# protoboard.net
KiCad netlist of a schematic drawn in EAGLE
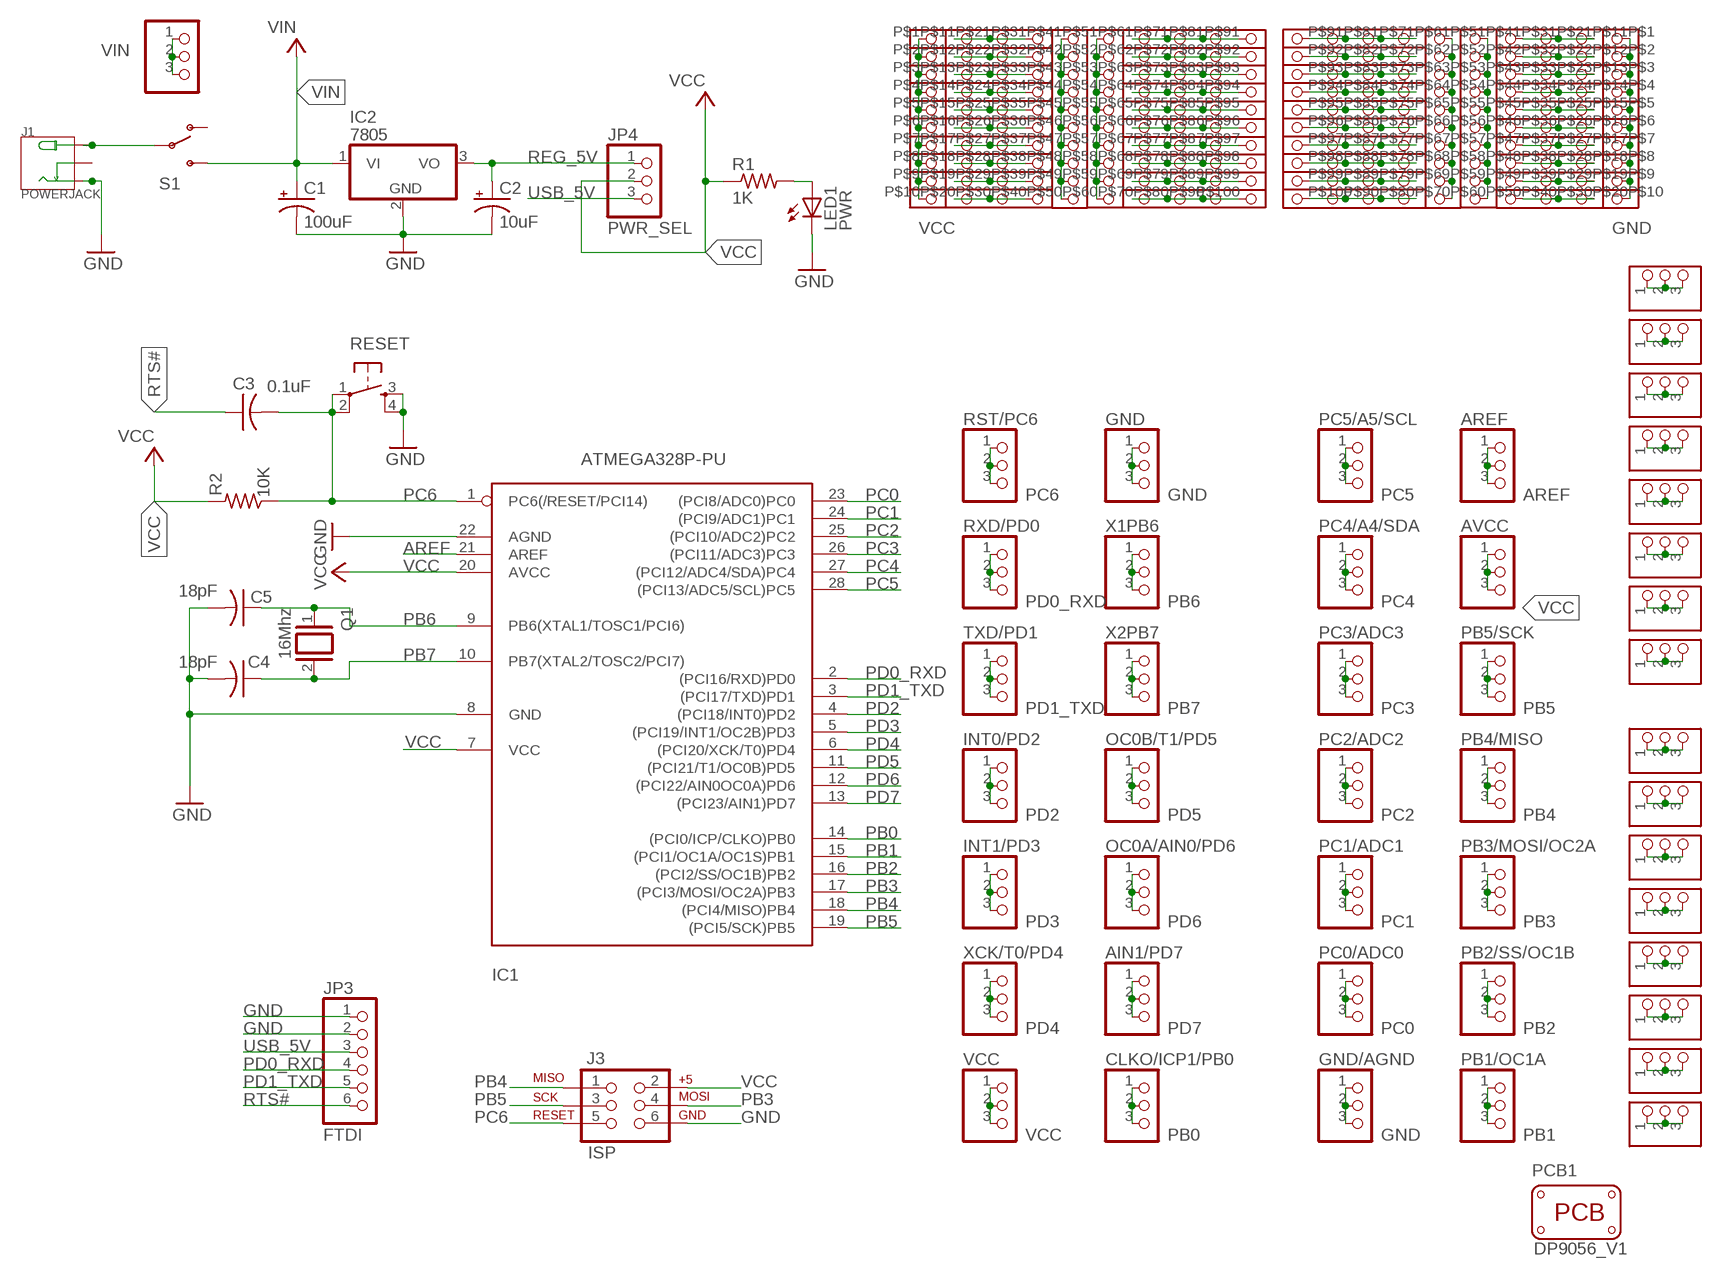
[diagram p0: schematic, sheet 1]

(export (version "E")
  (design (tool "Eeschema 10.0.6"))
  (components
    (comp (ref "AIN1/PD7")
      (value "PINHD-1X3")
      (footprint "eagle-import:1X03")
      (libsource (lib "eagle-import") (part "ubiyubix_PINHD-1X3"))
    )
    (comp (ref "AREF")
      (value "PINHD-1X3")
      (footprint "eagle-import:1X03")
      (libsource (lib "eagle-import") (part "ubiyubix_PINHD-1X3"))
    )
    (comp (ref "AVCC")
      (value "PINHD-1X3")
      (footprint "eagle-import:1X03")
      (libsource (lib "eagle-import") (part "ubiyubix_PINHD-1X3"))
    )
    (comp (ref "C1")
      (value "100uF")
      (footprint "eagle-import:CPOL-RADIAL-100UF-25V")
      (libsource (lib "eagle-import") (part "CAP_POLPTH1"))
    )
    (comp (ref "C2")
      (value "10uF")
      (footprint "eagle-import:CPOL-RADIAL-10UF-25V")
      (libsource (lib "eagle-import") (part "CAP_POLPTH2"))
    )
    (comp (ref "C3")
      (value "0.1uF")
      (footprint "eagle-import:C025-025X050")
      (libsource (lib "eagle-import") (part "C-US025-025X050"))
    )
    (comp (ref "C4")
      (value "18pF")
      (footprint "eagle-import:C025-025X050")
      (libsource (lib "eagle-import") (part "C-US025-025X050"))
    )
    (comp (ref "C5")
      (value "18pF")
      (footprint "eagle-import:C025-025X050")
      (libsource (lib "eagle-import") (part "C-US025-025X050"))
    )
    (comp (ref "CLKO/ICP1/PB0")
      (value "PINHD-1X3")
      (footprint "eagle-import:1X03")
      (libsource (lib "eagle-import") (part "ubiyubix_PINHD-1X3"))
    )
    (comp (ref "GND")
      (value "PINHD-1X3")
      (footprint "eagle-import:1X03")
      (libsource (lib "eagle-import") (part "ubiyubix_PINHD-1X3"))
    )
    (comp (ref "GND/AGND")
      (value "PINHD-1X3")
      (footprint "eagle-import:1X03")
      (libsource (lib "eagle-import") (part "ubiyubix_PINHD-1X3"))
    )
    (comp (ref "IC1")
      (value "ATMEGA328P-PU")
      (footprint "eagle-import:DIL28-3")
      (libsource (lib "eagle-import") (part "ATMEGA168P-20"))
    )
    (comp (ref "IC2")
      (value "7805")
      (footprint "eagle-import:TO220H")
      (libsource (lib "eagle-import") (part "78T05"))
    )
    (comp (ref "INT0/PD2")
      (value "PINHD-1X3")
      (footprint "eagle-import:1X03")
      (libsource (lib "eagle-import") (part "ubiyubix_PINHD-1X3"))
    )
    (comp (ref "INT1/PD3")
      (value "PINHD-1X3")
      (footprint "eagle-import:1X03")
      (libsource (lib "eagle-import") (part "ubiyubix_PINHD-1X3"))
    )
    (comp (ref "J1")
      (value "POWERJACK")
      (footprint "eagle-import:PW-3P-2.1")
      (libsource (lib "eagle-import") (part "JACK-DC-3P-3410020P1"))
    )
    (comp (ref "J3")
      (value "ISP")
      (footprint "eagle-import:2X3")
      (libsource (lib "eagle-import") (part "AVR_SPI_PRG_6PTH"))
    )
    (comp (ref "JP3")
      (value "FTDI")
      (footprint "eagle-import:1X06")
      (libsource (lib "eagle-import") (part "PINHD-1X6"))
    )
    (comp (ref "JP4")
      (value "PWR_SEL")
      (footprint "eagle-import:1X03")
      (libsource (lib "eagle-import") (part "PINHD-1X3"))
    )
    (comp (ref "LED1")
      (value "PWR")
      (footprint "eagle-import:LED3MM")
      (libsource (lib "eagle-import") (part "LED3MM"))
    )
    (comp (ref "OC0A/AIN0/PD6")
      (value "PINHD-1X3")
      (footprint "eagle-import:1X03")
      (libsource (lib "eagle-import") (part "ubiyubix_PINHD-1X3"))
    )
    (comp (ref "OC0B/T1/PD5")
      (value "PINHD-1X3")
      (footprint "eagle-import:1X03")
      (libsource (lib "eagle-import") (part "ubiyubix_PINHD-1X3"))
    )
    (comp (ref "PB1/OC1A")
      (value "PINHD-1X3")
      (footprint "eagle-import:1X03")
      (libsource (lib "eagle-import") (part "ubiyubix_PINHD-1X3"))
    )
    (comp (ref "PB2/SS/OC1B")
      (value "PINHD-1X3")
      (footprint "eagle-import:1X03")
      (libsource (lib "eagle-import") (part "ubiyubix_PINHD-1X3"))
    )
    (comp (ref "PB3/MOSI/OC2A")
      (value "PINHD-1X3")
      (footprint "eagle-import:1X03")
      (libsource (lib "eagle-import") (part "ubiyubix_PINHD-1X3"))
    )
    (comp (ref "PB4/MISO")
      (value "PINHD-1X3")
      (footprint "eagle-import:1X03")
      (libsource (lib "eagle-import") (part "ubiyubix_PINHD-1X3"))
    )
    (comp (ref "PB5/SCK")
      (value "PINHD-1X3")
      (footprint "eagle-import:1X03")
      (libsource (lib "eagle-import") (part "ubiyubix_PINHD-1X3"))
    )
    (comp (ref "PC0/ADC0")
      (value "PINHD-1X3")
      (footprint "eagle-import:1X03")
      (libsource (lib "eagle-import") (part "ubiyubix_PINHD-1X3"))
    )
    (comp (ref "PC1/ADC1")
      (value "PINHD-1X3")
      (footprint "eagle-import:1X03")
      (libsource (lib "eagle-import") (part "ubiyubix_PINHD-1X3"))
    )
    (comp (ref "PC2/ADC2")
      (value "PINHD-1X3")
      (footprint "eagle-import:1X03")
      (libsource (lib "eagle-import") (part "ubiyubix_PINHD-1X3"))
    )
    (comp (ref "PC3/ADC3")
      (value "PINHD-1X3")
      (footprint "eagle-import:1X03")
      (libsource (lib "eagle-import") (part "ubiyubix_PINHD-1X3"))
    )
    (comp (ref "PC4/A4/SDA")
      (value "PINHD-1X3")
      (footprint "eagle-import:1X03")
      (libsource (lib "eagle-import") (part "ubiyubix_PINHD-1X3"))
    )
    (comp (ref "PC5/A5/SCL")
      (value "PINHD-1X3")
      (footprint "eagle-import:1X03")
      (libsource (lib "eagle-import") (part "ubiyubix_PINHD-1X3"))
    )
    (comp (ref "PCB1")
      (value "PCB_DP_RECTANGLE-56X90")
      (footprint "eagle-import:DP9056_V1")
      (libsource (lib "eagle-import") (part "PCB_DP_RECTANGLE-56X90"))
    )
    (comp (ref "Q1")
      (value "16Mhz")
      (footprint "eagle-import:QS")
      (libsource (lib "eagle-import") (part "XTAL/S"))
    )
    (comp (ref "R1")
      (value "1K")
      (footprint "eagle-import:0207_7")
      (libsource (lib "eagle-import") (part "RESISTOR-1/4W"))
    )
    (comp (ref "R2")
      (value "10K")
      (footprint "eagle-import:0207_7")
      (libsource (lib "eagle-import") (part "RESISTOR-1/4W"))
    )
    (comp (ref "RESET")
      (value "TAC_SWITCHPTH")
      (footprint "eagle-import:TACTILE-PTH")
      (libsource (lib "eagle-import") (part "TAC_SWITCHPTH"))
    )
    (comp (ref "RST/PC6")
      (value "PINHD-1X3")
      (footprint "eagle-import:1X03")
      (libsource (lib "eagle-import") (part "ubiyubix_PINHD-1X3"))
    )
    (comp (ref "RXD/PD0")
      (value "PINHD-1X3")
      (footprint "eagle-import:1X03")
      (libsource (lib "eagle-import") (part "ubiyubix_PINHD-1X3"))
    )
    (comp (ref "S1")
      (value "SWITCH-SPDTPTH")
      (footprint "eagle-import:SWITCH-SPDT")
      (libsource (lib "eagle-import") (part "SWITCH-SPDTPTH"))
    )
    (comp (ref "TXD/PD1")
      (value "PINHD-1X3")
      (footprint "eagle-import:1X03")
      (libsource (lib "eagle-import") (part "ubiyubix_PINHD-1X3"))
    )
    (comp (ref "U$1")
      (value "PROTOFIELD-10X10")
      (footprint "eagle-import:PROTOFIELD-10X10")
      (libsource (lib "eagle-import") (part "PROTOFIELD-10X10"))
    )
    (comp (ref "U$3")
      (value "PROTOFIELD-10X10")
      (footprint "eagle-import:PROTOFIELD-10X10")
      (libsource (lib "eagle-import") (part "PROTOFIELD-10X10"))
    )
    (comp (ref "U$4")
      (value "PROTOFIELD-3")
      (footprint "eagle-import:PROTOFIELD-3")
      (libsource (lib "eagle-import") (part "PROTOFIELD-3"))
    )
    (comp (ref "U$5")
      (value "PROTOFIELD-3")
      (footprint "eagle-import:PROTOFIELD-3")
      (libsource (lib "eagle-import") (part "PROTOFIELD-3"))
    )
    (comp (ref "U$6")
      (value "PROTOFIELD-3")
      (footprint "eagle-import:PROTOFIELD-3")
      (libsource (lib "eagle-import") (part "PROTOFIELD-3"))
    )
    (comp (ref "U$7")
      (value "PROTOFIELD-3")
      (footprint "eagle-import:PROTOFIELD-3")
      (libsource (lib "eagle-import") (part "PROTOFIELD-3"))
    )
    (comp (ref "U$8")
      (value "PROTOFIELD-3")
      (footprint "eagle-import:PROTOFIELD-3")
      (libsource (lib "eagle-import") (part "PROTOFIELD-3"))
    )
    (comp (ref "U$9")
      (value "PROTOFIELD-3")
      (footprint "eagle-import:PROTOFIELD-3")
      (libsource (lib "eagle-import") (part "PROTOFIELD-3"))
    )
    (comp (ref "U$10")
      (value "PROTOFIELD-3")
      (footprint "eagle-import:PROTOFIELD-3")
      (libsource (lib "eagle-import") (part "PROTOFIELD-3"))
    )
    (comp (ref "U$11")
      (value "PROTOFIELD-3")
      (footprint "eagle-import:PROTOFIELD-3")
      (libsource (lib "eagle-import") (part "PROTOFIELD-3"))
    )
    (comp (ref "U$12")
      (value "PROTOFIELD-3")
      (footprint "eagle-import:PROTOFIELD-3")
      (libsource (lib "eagle-import") (part "PROTOFIELD-3"))
    )
    (comp (ref "U$13")
      (value "PROTOFIELD-3")
      (footprint "eagle-import:PROTOFIELD-3")
      (libsource (lib "eagle-import") (part "PROTOFIELD-3"))
    )
    (comp (ref "U$14")
      (value "PROTOFIELD-3")
      (footprint "eagle-import:PROTOFIELD-3")
      (libsource (lib "eagle-import") (part "PROTOFIELD-3"))
    )
    (comp (ref "U$15")
      (value "PROTOFIELD-3")
      (footprint "eagle-import:PROTOFIELD-3")
      (libsource (lib "eagle-import") (part "PROTOFIELD-3"))
    )
    (comp (ref "U$16")
      (value "PROTOFIELD-3")
      (footprint "eagle-import:PROTOFIELD-3")
      (libsource (lib "eagle-import") (part "PROTOFIELD-3"))
    )
    (comp (ref "U$17")
      (value "PROTOFIELD-3")
      (footprint "eagle-import:PROTOFIELD-3")
      (libsource (lib "eagle-import") (part "PROTOFIELD-3"))
    )
    (comp (ref "U$18")
      (value "PROTOFIELD-3")
      (footprint "eagle-import:PROTOFIELD-3")
      (libsource (lib "eagle-import") (part "PROTOFIELD-3"))
    )
    (comp (ref "U$19")
      (value "PROTOFIELD-3")
      (footprint "eagle-import:PROTOFIELD-3")
      (libsource (lib "eagle-import") (part "PROTOFIELD-3"))
    )
    (comp (ref "VCC")
      (value "PINHD-1X3")
      (footprint "eagle-import:1X03")
      (libsource (lib "eagle-import") (part "ubiyubix_PINHD-1X3"))
    )
    (comp (ref "VIN")
      (value "+9V")
      (footprint "eagle-import:1X03")
      (libsource (lib "eagle-import") (part "ubiyubix_PINHD-1X3"))
    )
    (comp (ref "X1PB6")
      (value "PINHD-1X3")
      (footprint "eagle-import:1X03")
      (libsource (lib "eagle-import") (part "ubiyubix_PINHD-1X3"))
    )
    (comp (ref "X2PB7")
      (value "PINHD-1X3")
      (footprint "eagle-import:1X03")
      (libsource (lib "eagle-import") (part "ubiyubix_PINHD-1X3"))
    )
    (comp (ref "XCK/T0/PD4")
      (value "PINHD-1X3")
      (footprint "eagle-import:1X03")
      (libsource (lib "eagle-import") (part "ubiyubix_PINHD-1X3"))
    )
  )
  (nets
    (net (code "1") (name "/AREF") (class "Default")
      (node (ref "AREF") (pin "1") (pinfunction "1_1") (pintype "passive"))
      (node (ref "AREF") (pin "2") (pinfunction "2_2") (pintype "passive"))
      (node (ref "AREF") (pin "3") (pinfunction "3_3") (pintype "passive"))
      (node (ref "IC1") (pin "21") (pinfunction "AREF_21") (pintype "bidirectional"))
    )
    (net (code "2") (name "/PB0") (class "Default")
      (node (ref "CLKO/ICP1/PB0") (pin "1") (pinfunction "1_1") (pintype "passive"))
      (node (ref "CLKO/ICP1/PB0") (pin "2") (pinfunction "2_2") (pintype "passive"))
      (node (ref "CLKO/ICP1/PB0") (pin "3") (pinfunction "3_3") (pintype "passive"))
      (node (ref "IC1") (pin "14") (pinfunction "(PCI0/ICP/CLKO)PB0_14") (pintype "bidirectional"))
    )
    (net (code "3") (name "/PB1") (class "Default")
      (node (ref "IC1") (pin "15") (pinfunction "(PCI1/OC1A/OC1S)PB1_15") (pintype "bidirectional"))
      (node (ref "PB1/OC1A") (pin "1") (pinfunction "1_1") (pintype "passive"))
      (node (ref "PB1/OC1A") (pin "2") (pinfunction "2_2") (pintype "passive"))
      (node (ref "PB1/OC1A") (pin "3") (pinfunction "3_3") (pintype "passive"))
    )
    (net (code "4") (name "/PB2") (class "Default")
      (node (ref "IC1") (pin "16") (pinfunction "(PCI2/SS/OC1B)PB2_16") (pintype "bidirectional"))
      (node (ref "PB2/SS/OC1B") (pin "1") (pinfunction "1_1") (pintype "passive"))
      (node (ref "PB2/SS/OC1B") (pin "2") (pinfunction "2_2") (pintype "passive"))
      (node (ref "PB2/SS/OC1B") (pin "3") (pinfunction "3_3") (pintype "passive"))
    )
    (net (code "5") (name "/PB3") (class "Default")
      (node (ref "IC1") (pin "17") (pinfunction "(PCI3/MOSI/OC2A)PB3_17") (pintype "bidirectional"))
      (node (ref "J3") (pin "4") (pinfunction "4_4") (pintype "passive"))
      (node (ref "PB3/MOSI/OC2A") (pin "1") (pinfunction "1_1") (pintype "passive"))
      (node (ref "PB3/MOSI/OC2A") (pin "2") (pinfunction "2_2") (pintype "passive"))
      (node (ref "PB3/MOSI/OC2A") (pin "3") (pinfunction "3_3") (pintype "passive"))
    )
    (net (code "6") (name "/PB4") (class "Default")
      (node (ref "IC1") (pin "18") (pinfunction "(PCI4/MISO)PB4_18") (pintype "bidirectional"))
      (node (ref "J3") (pin "1") (pinfunction "1_1") (pintype "passive"))
      (node (ref "PB4/MISO") (pin "1") (pinfunction "1_1") (pintype "passive"))
      (node (ref "PB4/MISO") (pin "2") (pinfunction "2_2") (pintype "passive"))
      (node (ref "PB4/MISO") (pin "3") (pinfunction "3_3") (pintype "passive"))
    )
    (net (code "7") (name "/PB5") (class "Default")
      (node (ref "IC1") (pin "19") (pinfunction "(PCI5/SCK)PB5_19") (pintype "bidirectional"))
      (node (ref "J3") (pin "3") (pinfunction "3_3") (pintype "passive"))
      (node (ref "PB5/SCK") (pin "1") (pinfunction "1_1") (pintype "passive"))
      (node (ref "PB5/SCK") (pin "2") (pinfunction "2_2") (pintype "passive"))
      (node (ref "PB5/SCK") (pin "3") (pinfunction "3_3") (pintype "passive"))
    )
    (net (code "8") (name "/PB6") (class "Default")
      (node (ref "C5") (pin "1") (pinfunction "1_1") (pintype "passive"))
      (node (ref "IC1") (pin "9") (pinfunction "PB6(XTAL1/TOSC1/PCI6)_9") (pintype "bidirectional"))
      (node (ref "Q1") (pin "1") (pinfunction "1_1") (pintype "passive"))
      (node (ref "X1PB6") (pin "1") (pinfunction "1_1") (pintype "passive"))
      (node (ref "X1PB6") (pin "2") (pinfunction "2_2") (pintype "passive"))
      (node (ref "X1PB6") (pin "3") (pinfunction "3_3") (pintype "passive"))
    )
    (net (code "9") (name "/PB7") (class "Default")
      (node (ref "C4") (pin "1") (pinfunction "1_1") (pintype "passive"))
      (node (ref "IC1") (pin "10") (pinfunction "PB7(XTAL2/TOSC2/PCI7)_10") (pintype "bidirectional"))
      (node (ref "Q1") (pin "2") (pinfunction "2_2") (pintype "passive"))
      (node (ref "X2PB7") (pin "1") (pinfunction "1_1") (pintype "passive"))
      (node (ref "X2PB7") (pin "2") (pinfunction "2_2") (pintype "passive"))
      (node (ref "X2PB7") (pin "3") (pinfunction "3_3") (pintype "passive"))
    )
    (net (code "10") (name "/PC0") (class "Default")
      (node (ref "IC1") (pin "23") (pinfunction "(PCI8/ADC0)PC0_23") (pintype "bidirectional"))
      (node (ref "PC0/ADC0") (pin "1") (pinfunction "1_1") (pintype "passive"))
      (node (ref "PC0/ADC0") (pin "2") (pinfunction "2_2") (pintype "passive"))
      (node (ref "PC0/ADC0") (pin "3") (pinfunction "3_3") (pintype "passive"))
    )
    (net (code "11") (name "/PC1") (class "Default")
      (node (ref "IC1") (pin "24") (pinfunction "(PCI9/ADC1)PC1_24") (pintype "bidirectional"))
      (node (ref "PC1/ADC1") (pin "1") (pinfunction "1_1") (pintype "passive"))
      (node (ref "PC1/ADC1") (pin "2") (pinfunction "2_2") (pintype "passive"))
      (node (ref "PC1/ADC1") (pin "3") (pinfunction "3_3") (pintype "passive"))
    )
    (net (code "12") (name "/PC2") (class "Default")
      (node (ref "IC1") (pin "25") (pinfunction "(PCI10/ADC2)PC2_25") (pintype "bidirectional"))
      (node (ref "PC2/ADC2") (pin "1") (pinfunction "1_1") (pintype "passive"))
      (node (ref "PC2/ADC2") (pin "2") (pinfunction "2_2") (pintype "passive"))
      (node (ref "PC2/ADC2") (pin "3") (pinfunction "3_3") (pintype "passive"))
    )
    (net (code "13") (name "/PC3") (class "Default")
      (node (ref "IC1") (pin "26") (pinfunction "(PCI11/ADC3)PC3_26") (pintype "bidirectional"))
      (node (ref "PC3/ADC3") (pin "1") (pinfunction "1_1") (pintype "passive"))
      (node (ref "PC3/ADC3") (pin "2") (pinfunction "2_2") (pintype "passive"))
      (node (ref "PC3/ADC3") (pin "3") (pinfunction "3_3") (pintype "passive"))
    )
    (net (code "14") (name "/PC4") (class "Default")
      (node (ref "IC1") (pin "27") (pinfunction "(PCI12/ADC4/SDA)PC4_27") (pintype "bidirectional"))
      (node (ref "PC4/A4/SDA") (pin "1") (pinfunction "1_1") (pintype "passive"))
      (node (ref "PC4/A4/SDA") (pin "2") (pinfunction "2_2") (pintype "passive"))
      (node (ref "PC4/A4/SDA") (pin "3") (pinfunction "3_3") (pintype "passive"))
    )
    (net (code "15") (name "/PC5") (class "Default")
      (node (ref "IC1") (pin "28") (pinfunction "(PCI13/ADC5/SCL)PC5_28") (pintype "bidirectional"))
      (node (ref "PC5/A5/SCL") (pin "1") (pinfunction "1_1") (pintype "passive"))
      (node (ref "PC5/A5/SCL") (pin "2") (pinfunction "2_2") (pintype "passive"))
      (node (ref "PC5/A5/SCL") (pin "3") (pinfunction "3_3") (pintype "passive"))
    )
    (net (code "16") (name "/PC6") (class "Default")
      (node (ref "C3") (pin "2") (pinfunction "2_2") (pintype "passive"))
      (node (ref "IC1") (pin "1") (pinfunction "PC6(/RESET/PCI14)_1") (pintype "bidirectional"))
      (node (ref "J3") (pin "5") (pinfunction "5_5") (pintype "passive"))
      (node (ref "R2") (pin "1") (pinfunction "1_1") (pintype "passive"))
      (node (ref "RESET") (pin "1") (pinfunction "1_1") (pintype "passive"))
      (node (ref "RESET") (pin "2") (pinfunction "2_2") (pintype "passive"))
      (node (ref "RST/PC6") (pin "1") (pinfunction "1_1") (pintype "passive"))
      (node (ref "RST/PC6") (pin "2") (pinfunction "2_2") (pintype "passive"))
      (node (ref "RST/PC6") (pin "3") (pinfunction "3_3") (pintype "passive"))
    )
    (net (code "17") (name "/PD0_RXD") (class "Default")
      (node (ref "IC1") (pin "2") (pinfunction "(PCI16/RXD)PD0_2") (pintype "bidirectional"))
      (node (ref "JP3") (pin "4") (pinfunction "4_4") (pintype "passive"))
      (node (ref "RXD/PD0") (pin "1") (pinfunction "1_1") (pintype "passive"))
      (node (ref "RXD/PD0") (pin "2") (pinfunction "2_2") (pintype "passive"))
      (node (ref "RXD/PD0") (pin "3") (pinfunction "3_3") (pintype "passive"))
    )
    (net (code "18") (name "/PD1_TXD") (class "Default")
      (node (ref "IC1") (pin "3") (pinfunction "(PCI17/TXD)PD1_3") (pintype "bidirectional"))
      (node (ref "JP3") (pin "5") (pinfunction "5_5") (pintype "passive"))
      (node (ref "TXD/PD1") (pin "1") (pinfunction "1_1") (pintype "passive"))
      (node (ref "TXD/PD1") (pin "2") (pinfunction "2_2") (pintype "passive"))
      (node (ref "TXD/PD1") (pin "3") (pinfunction "3_3") (pintype "passive"))
    )
    (net (code "19") (name "/PD2") (class "Default")
      (node (ref "IC1") (pin "4") (pinfunction "(PCI18/INT0)PD2_4") (pintype "bidirectional"))
      (node (ref "INT0/PD2") (pin "1") (pinfunction "1_1") (pintype "passive"))
      (node (ref "INT0/PD2") (pin "2") (pinfunction "2_2") (pintype "passive"))
      (node (ref "INT0/PD2") (pin "3") (pinfunction "3_3") (pintype "passive"))
    )
    (net (code "20") (name "/PD3") (class "Default")
      (node (ref "IC1") (pin "5") (pinfunction "(PCI19/INT1/OC2B)PD3_5") (pintype "bidirectional"))
      (node (ref "INT1/PD3") (pin "1") (pinfunction "1_1") (pintype "passive"))
      (node (ref "INT1/PD3") (pin "2") (pinfunction "2_2") (pintype "passive"))
      (node (ref "INT1/PD3") (pin "3") (pinfunction "3_3") (pintype "passive"))
    )
    (net (code "21") (name "/PD4") (class "Default")
      (node (ref "IC1") (pin "6") (pinfunction "(PCI20/XCK/T0)PD4_6") (pintype "bidirectional"))
      (node (ref "XCK/T0/PD4") (pin "1") (pinfunction "1_1") (pintype "passive"))
      (node (ref "XCK/T0/PD4") (pin "2") (pinfunction "2_2") (pintype "passive"))
      (node (ref "XCK/T0/PD4") (pin "3") (pinfunction "3_3") (pintype "passive"))
    )
    (net (code "22") (name "/PD5") (class "Default")
      (node (ref "IC1") (pin "11") (pinfunction "(PCI21/T1/OC0B)PD5_11") (pintype "bidirectional"))
      (node (ref "OC0B/T1/PD5") (pin "1") (pinfunction "1_1") (pintype "passive"))
      (node (ref "OC0B/T1/PD5") (pin "2") (pinfunction "2_2") (pintype "passive"))
      (node (ref "OC0B/T1/PD5") (pin "3") (pinfunction "3_3") (pintype "passive"))
    )
    (net (code "23") (name "/PD6") (class "Default")
      (node (ref "IC1") (pin "12") (pinfunction "(PCI22/AIN0OC0A)PD6_12") (pintype "bidirectional"))
      (node (ref "OC0A/AIN0/PD6") (pin "1") (pinfunction "1_1") (pintype "passive"))
      (node (ref "OC0A/AIN0/PD6") (pin "2") (pinfunction "2_2") (pintype "passive"))
      (node (ref "OC0A/AIN0/PD6") (pin "3") (pinfunction "3_3") (pintype "passive"))
    )
    (net (code "24") (name "/PD7") (class "Default")
      (node (ref "AIN1/PD7") (pin "1") (pinfunction "1_1") (pintype "passive"))
      (node (ref "AIN1/PD7") (pin "2") (pinfunction "2_2") (pintype "passive"))
      (node (ref "AIN1/PD7") (pin "3") (pinfunction "3_3") (pintype "passive"))
      (node (ref "IC1") (pin "13") (pinfunction "(PCI23/AIN1)PD7_13") (pintype "bidirectional"))
    )
    (net (code "25") (name "/REG_5V") (class "Default")
      (node (ref "C2") (pin "1") (pinfunction "+_1") (pintype "passive"))
      (node (ref "IC2") (pin "3") (pinfunction "VO_3") (pintype "passive"))
      (node (ref "JP4") (pin "1") (pinfunction "1_1") (pintype "passive"))
    )
    (net (code "26") (name "/USB_5V") (class "Default")
      (node (ref "JP3") (pin "3") (pinfunction "3_3") (pintype "passive"))
      (node (ref "JP4") (pin "3") (pinfunction "3_3") (pintype "passive"))
    )
    (net (code "27") (name "GND") (class "Default")
      (node (ref "C1") (pin "2") (pinfunction "-_2") (pintype "passive"))
      (node (ref "C2") (pin "2") (pinfunction "-_2") (pintype "passive"))
      (node (ref "C4") (pin "2") (pinfunction "2_2") (pintype "passive"))
      (node (ref "C5") (pin "2") (pinfunction "2_2") (pintype "passive"))
      (node (ref "GND") (pin "1") (pinfunction "1_1") (pintype "passive"))
      (node (ref "GND") (pin "2") (pinfunction "2_2") (pintype "passive"))
      (node (ref "GND") (pin "3") (pinfunction "3_3") (pintype "passive"))
      (node (ref "GND/AGND") (pin "1") (pinfunction "1_1") (pintype "passive"))
      (node (ref "GND/AGND") (pin "2") (pinfunction "2_2") (pintype "passive"))
      (node (ref "GND/AGND") (pin "3") (pinfunction "3_3") (pintype "passive"))
      (node (ref "IC1") (pin "22") (pinfunction "AGND_22") (pintype "bidirectional"))
      (node (ref "IC1") (pin "8") (pinfunction "GND_8") (pintype "bidirectional"))
      (node (ref "IC2") (pin "2") (pinfunction "GND_2") (pintype "passive"))
      (node (ref "J1") (pin "-1") (pinfunction "-_-1") (pintype "bidirectional"))
      (node (ref "J3") (pin "6") (pinfunction "6_6") (pintype "passive"))
      (node (ref "JP3") (pin "1") (pinfunction "1_1") (pintype "passive"))
      (node (ref "JP3") (pin "2") (pinfunction "2_2") (pintype "passive"))
      (node (ref "LED1") (pin "K") (pinfunction "C_K") (pintype "passive"))
      (node (ref "RESET") (pin "3") (pinfunction "3_3") (pintype "passive"))
      (node (ref "RESET") (pin "4") (pinfunction "4_4") (pintype "passive"))
      (node (ref "U$3") (pin "P$1") (pinfunction "1_P$1") (pintype "passive"))
      (node (ref "U$3") (pin "P$10") (pinfunction "P$10_P$10") (pintype "passive"))
      (node (ref "U$3") (pin "P$2") (pinfunction "5_P$2") (pintype "passive"))
      (node (ref "U$3") (pin "P$3") (pinfunction "P$3_P$3") (pintype "passive"))
      (node (ref "U$3") (pin "P$4") (pinfunction "P$4_P$4") (pintype "passive"))
      (node (ref "U$3") (pin "P$5") (pinfunction "P$5_P$5") (pintype "passive"))
      (node (ref "U$3") (pin "P$6") (pinfunction "P$6_P$6") (pintype "passive"))
      (node (ref "U$3") (pin "P$7") (pinfunction "P$7_P$7") (pintype "passive"))
      (node (ref "U$3") (pin "P$8") (pinfunction "P$8_P$8") (pintype "passive"))
      (node (ref "U$3") (pin "P$9") (pinfunction "P$9_P$9") (pintype "passive"))
    )
    (net (code "28") (name "Net-(LED1-PadA)") (class "Default")
      (node (ref "LED1") (pin "A") (pinfunction "A_A") (pintype "passive"))
      (node (ref "R1") (pin "2") (pinfunction "2_2") (pintype "passive"))
    )
    (net (code "29") (name "Net-(S1-P)") (class "Default")
      (node (ref "J1") (pin "+") (pinfunction "+_+") (pintype "bidirectional"))
      (node (ref "S1") (pin "2") (pinfunction "P_2") (pintype "passive"))
    )
    (net (code "30") (name "Net-(U$1-2)") (class "Default")
      (node (ref "U$1") (pin "P$11") (pinfunction "2_P$11") (pintype "passive"))
      (node (ref "U$1") (pin "P$21") (pinfunction "3_P$21") (pintype "passive"))
      (node (ref "U$1") (pin "P$31") (pinfunction "4_P$31") (pintype "passive"))
    )
    (net (code "31") (name "Net-(U$1-6)") (class "Default")
      (node (ref "U$1") (pin "P$12") (pinfunction "6_P$12") (pintype "passive"))
      (node (ref "U$1") (pin "P$22") (pinfunction "7_P$22") (pintype "passive"))
      (node (ref "U$1") (pin "P$32") (pinfunction "8_P$32") (pintype "passive"))
    )
    (net (code "32") (name "Net-(U$1-PadP$13)") (class "Default")
      (node (ref "U$1") (pin "P$13") (pinfunction "P$13_P$13") (pintype "passive"))
      (node (ref "U$1") (pin "P$23") (pinfunction "P$23_P$23") (pintype "passive"))
      (node (ref "U$1") (pin "P$33") (pinfunction "P$33_P$33") (pintype "passive"))
    )
    (net (code "33") (name "Net-(U$1-PadP$14)") (class "Default")
      (node (ref "U$1") (pin "P$14") (pinfunction "P$14_P$14") (pintype "passive"))
      (node (ref "U$1") (pin "P$24") (pinfunction "P$24_P$24") (pintype "passive"))
      (node (ref "U$1") (pin "P$34") (pinfunction "P$34_P$34") (pintype "passive"))
    )
    (net (code "34") (name "Net-(U$1-PadP$15)") (class "Default")
      (node (ref "U$1") (pin "P$15") (pinfunction "P$15_P$15") (pintype "passive"))
      (node (ref "U$1") (pin "P$25") (pinfunction "P$25_P$25") (pintype "passive"))
      (node (ref "U$1") (pin "P$35") (pinfunction "P$35_P$35") (pintype "passive"))
    )
    (net (code "35") (name "Net-(U$1-PadP$16)") (class "Default")
      (node (ref "U$1") (pin "P$16") (pinfunction "P$16_P$16") (pintype "passive"))
      (node (ref "U$1") (pin "P$26") (pinfunction "P$26_P$26") (pintype "passive"))
      (node (ref "U$1") (pin "P$36") (pinfunction "P$36_P$36") (pintype "passive"))
    )
    (net (code "36") (name "Net-(U$1-PadP$17)") (class "Default")
      (node (ref "U$1") (pin "P$17") (pinfunction "P$17_P$17") (pintype "passive"))
      (node (ref "U$1") (pin "P$27") (pinfunction "P$27_P$27") (pintype "passive"))
      (node (ref "U$1") (pin "P$37") (pinfunction "P$37_P$37") (pintype "passive"))
    )
    (net (code "37") (name "Net-(U$1-PadP$18)") (class "Default")
      (node (ref "U$1") (pin "P$18") (pinfunction "P$18_P$18") (pintype "passive"))
      (node (ref "U$1") (pin "P$28") (pinfunction "P$28_P$28") (pintype "passive"))
      (node (ref "U$1") (pin "P$38") (pinfunction "P$38_P$38") (pintype "passive"))
    )
    (net (code "38") (name "Net-(U$1-PadP$19)") (class "Default")
      (node (ref "U$1") (pin "P$19") (pinfunction "P$19_P$19") (pintype "passive"))
      (node (ref "U$1") (pin "P$29") (pinfunction "P$29_P$29") (pintype "passive"))
      (node (ref "U$1") (pin "P$39") (pinfunction "P$39_P$39") (pintype "passive"))
    )
    (net (code "39") (name "Net-(U$1-PadP$20)") (class "Default")
      (node (ref "U$1") (pin "P$20") (pinfunction "P$20_P$20") (pintype "passive"))
      (node (ref "U$1") (pin "P$30") (pinfunction "P$30_P$30") (pintype "passive"))
      (node (ref "U$1") (pin "P$40") (pinfunction "P$40_P$40") (pintype "passive"))
    )
    (net (code "40") (name "Net-(U$1-PadP$41)") (class "Default")
      (node (ref "U$1") (pin "P$41") (pinfunction "P$41_P$41") (pintype "passive"))
      (node (ref "U$1") (pin "P$42") (pinfunction "P$42_P$42") (pintype "passive"))
      (node (ref "U$1") (pin "P$43") (pinfunction "P$43_P$43") (pintype "passive"))
      (node (ref "U$1") (pin "P$44") (pinfunction "P$44_P$44") (pintype "passive"))
      (node (ref "U$1") (pin "P$45") (pinfunction "P$45_P$45") (pintype "passive"))
      (node (ref "U$1") (pin "P$46") (pinfunction "P$46_P$46") (pintype "passive"))
      (node (ref "U$1") (pin "P$47") (pinfunction "P$47_P$47") (pintype "passive"))
      (node (ref "U$1") (pin "P$48") (pinfunction "P$48_P$48") (pintype "passive"))
      (node (ref "U$1") (pin "P$49") (pinfunction "P$49_P$49") (pintype "passive"))
      (node (ref "U$1") (pin "P$50") (pinfunction "P$50_P$50") (pintype "passive"))
    )
    (net (code "41") (name "Net-(U$1-PadP$51)") (class "Default")
      (node (ref "U$1") (pin "P$51") (pinfunction "P$51_P$51") (pintype "passive"))
      (node (ref "U$1") (pin "P$52") (pinfunction "P$52_P$52") (pintype "passive"))
      (node (ref "U$1") (pin "P$53") (pinfunction "P$53_P$53") (pintype "passive"))
      (node (ref "U$1") (pin "P$54") (pinfunction "P$54_P$54") (pintype "passive"))
      (node (ref "U$1") (pin "P$55") (pinfunction "P$55_P$55") (pintype "passive"))
      (node (ref "U$1") (pin "P$56") (pinfunction "P$56_P$56") (pintype "passive"))
      (node (ref "U$1") (pin "P$57") (pinfunction "P$57_P$57") (pintype "passive"))
      (node (ref "U$1") (pin "P$58") (pinfunction "P$58_P$58") (pintype "passive"))
      (node (ref "U$1") (pin "P$59") (pinfunction "P$59_P$59") (pintype "passive"))
      (node (ref "U$1") (pin "P$60") (pinfunction "P$60_P$60") (pintype "passive"))
    )
    (net (code "42") (name "Net-(U$1-PadP$61)") (class "Default")
      (node (ref "U$1") (pin "P$61") (pinfunction "P$61_P$61") (pintype "passive"))
      (node (ref "U$1") (pin "P$71") (pinfunction "P$71_P$71") (pintype "passive"))
      (node (ref "U$1") (pin "P$81") (pinfunction "P$81_P$81") (pintype "passive"))
      (node (ref "U$1") (pin "P$91") (pinfunction "P$91_P$91") (pintype "passive"))
    )
    (net (code "43") (name "Net-(U$1-PadP$62)") (class "Default")
      (node (ref "U$1") (pin "P$62") (pinfunction "P$62_P$62") (pintype "passive"))
      (node (ref "U$1") (pin "P$72") (pinfunction "P$72_P$72") (pintype "passive"))
      (node (ref "U$1") (pin "P$82") (pinfunction "P$82_P$82") (pintype "passive"))
      (node (ref "U$1") (pin "P$92") (pinfunction "P$92_P$92") (pintype "passive"))
    )
    (net (code "44") (name "Net-(U$1-PadP$63)") (class "Default")
      (node (ref "U$1") (pin "P$63") (pinfunction "P$63_P$63") (pintype "passive"))
      (node (ref "U$1") (pin "P$73") (pinfunction "P$73_P$73") (pintype "passive"))
      (node (ref "U$1") (pin "P$83") (pinfunction "P$83_P$83") (pintype "passive"))
      (node (ref "U$1") (pin "P$93") (pinfunction "P$93_P$93") (pintype "passive"))
    )
    (net (code "45") (name "Net-(U$1-PadP$64)") (class "Default")
      (node (ref "U$1") (pin "P$64") (pinfunction "P$64_P$64") (pintype "passive"))
      (node (ref "U$1") (pin "P$74") (pinfunction "P$74_P$74") (pintype "passive"))
      (node (ref "U$1") (pin "P$84") (pinfunction "P$84_P$84") (pintype "passive"))
      (node (ref "U$1") (pin "P$94") (pinfunction "P$94_P$94") (pintype "passive"))
    )
    (net (code "46") (name "Net-(U$1-PadP$65)") (class "Default")
      (node (ref "U$1") (pin "P$65") (pinfunction "P$65_P$65") (pintype "passive"))
      (node (ref "U$1") (pin "P$75") (pinfunction "P$75_P$75") (pintype "passive"))
      (node (ref "U$1") (pin "P$85") (pinfunction "P$85_P$85") (pintype "passive"))
      (node (ref "U$1") (pin "P$95") (pinfunction "P$95_P$95") (pintype "passive"))
    )
    (net (code "47") (name "Net-(U$1-PadP$66)") (class "Default")
      (node (ref "U$1") (pin "P$66") (pinfunction "P$66_P$66") (pintype "passive"))
      (node (ref "U$1") (pin "P$76") (pinfunction "P$76_P$76") (pintype "passive"))
      (node (ref "U$1") (pin "P$86") (pinfunction "P$86_P$86") (pintype "passive"))
      (node (ref "U$1") (pin "P$96") (pinfunction "P$96_P$96") (pintype "passive"))
    )
    (net (code "48") (name "Net-(U$1-PadP$67)") (class "Default")
      (node (ref "U$1") (pin "P$67") (pinfunction "P$67_P$67") (pintype "passive"))
      (node (ref "U$1") (pin "P$77") (pinfunction "P$77_P$77") (pintype "passive"))
      (node (ref "U$1") (pin "P$87") (pinfunction "P$87_P$87") (pintype "passive"))
      (node (ref "U$1") (pin "P$97") (pinfunction "P$97_P$97") (pintype "passive"))
    )
    (net (code "49") (name "Net-(U$1-PadP$68)") (class "Default")
      (node (ref "U$1") (pin "P$68") (pinfunction "P$68_P$68") (pintype "passive"))
      (node (ref "U$1") (pin "P$78") (pinfunction "P$78_P$78") (pintype "passive"))
      (node (ref "U$1") (pin "P$88") (pinfunction "P$88_P$88") (pintype "passive"))
      (node (ref "U$1") (pin "P$98") (pinfunction "P$98_P$98") (pintype "passive"))
    )
    (net (code "50") (name "Net-(U$1-PadP$69)") (class "Default")
      (node (ref "U$1") (pin "P$69") (pinfunction "P$69_P$69") (pintype "passive"))
      (node (ref "U$1") (pin "P$79") (pinfunction "P$79_P$79") (pintype "passive"))
      (node (ref "U$1") (pin "P$89") (pinfunction "P$89_P$89") (pintype "passive"))
      (node (ref "U$1") (pin "P$99") (pinfunction "P$99_P$99") (pintype "passive"))
    )
    (net (code "51") (name "Net-(U$1-PadP$100)") (class "Default")
      (node (ref "U$1") (pin "P$100") (pinfunction "P$100_P$100") (pintype "passive"))
      (node (ref "U$1") (pin "P$70") (pinfunction "P$70_P$70") (pintype "passive"))
      (node (ref "U$1") (pin "P$80") (pinfunction "P$80_P$80") (pintype "passive"))
      (node (ref "U$1") (pin "P$90") (pinfunction "P$90_P$90") (pintype "passive"))
    )
    (net (code "52") (name "Net-(U$3-2)") (class "Default")
      (node (ref "U$3") (pin "P$11") (pinfunction "2_P$11") (pintype "passive"))
      (node (ref "U$3") (pin "P$21") (pinfunction "3_P$21") (pintype "passive"))
      (node (ref "U$3") (pin "P$31") (pinfunction "4_P$31") (pintype "passive"))
    )
    (net (code "53") (name "Net-(U$3-6)") (class "Default")
      (node (ref "U$3") (pin "P$12") (pinfunction "6_P$12") (pintype "passive"))
      (node (ref "U$3") (pin "P$22") (pinfunction "7_P$22") (pintype "passive"))
      (node (ref "U$3") (pin "P$32") (pinfunction "8_P$32") (pintype "passive"))
    )
    (net (code "54") (name "Net-(U$3-PadP$13)") (class "Default")
      (node (ref "U$3") (pin "P$13") (pinfunction "P$13_P$13") (pintype "passive"))
      (node (ref "U$3") (pin "P$23") (pinfunction "P$23_P$23") (pintype "passive"))
      (node (ref "U$3") (pin "P$33") (pinfunction "P$33_P$33") (pintype "passive"))
    )
    (net (code "55") (name "Net-(U$3-PadP$14)") (class "Default")
      (node (ref "U$3") (pin "P$14") (pinfunction "P$14_P$14") (pintype "passive"))
      (node (ref "U$3") (pin "P$24") (pinfunction "P$24_P$24") (pintype "passive"))
      (node (ref "U$3") (pin "P$34") (pinfunction "P$34_P$34") (pintype "passive"))
    )
    (net (code "56") (name "Net-(U$3-PadP$15)") (class "Default")
      (node (ref "U$3") (pin "P$15") (pinfunction "P$15_P$15") (pintype "passive"))
      (node (ref "U$3") (pin "P$25") (pinfunction "P$25_P$25") (pintype "passive"))
      (node (ref "U$3") (pin "P$35") (pinfunction "P$35_P$35") (pintype "passive"))
    )
    (net (code "57") (name "Net-(U$3-PadP$16)") (class "Default")
      (node (ref "U$3") (pin "P$16") (pinfunction "P$16_P$16") (pintype "passive"))
      (node (ref "U$3") (pin "P$26") (pinfunction "P$26_P$26") (pintype "passive"))
      (node (ref "U$3") (pin "P$36") (pinfunction "P$36_P$36") (pintype "passive"))
    )
    (net (code "58") (name "Net-(U$3-PadP$17)") (class "Default")
      (node (ref "U$3") (pin "P$17") (pinfunction "P$17_P$17") (pintype "passive"))
      (node (ref "U$3") (pin "P$27") (pinfunction "P$27_P$27") (pintype "passive"))
      (node (ref "U$3") (pin "P$37") (pinfunction "P$37_P$37") (pintype "passive"))
    )
    (net (code "59") (name "Net-(U$3-PadP$18)") (class "Default")
      (node (ref "U$3") (pin "P$18") (pinfunction "P$18_P$18") (pintype "passive"))
      (node (ref "U$3") (pin "P$28") (pinfunction "P$28_P$28") (pintype "passive"))
      (node (ref "U$3") (pin "P$38") (pinfunction "P$38_P$38") (pintype "passive"))
    )
    (net (code "60") (name "Net-(U$3-PadP$19)") (class "Default")
      (node (ref "U$3") (pin "P$19") (pinfunction "P$19_P$19") (pintype "passive"))
      (node (ref "U$3") (pin "P$29") (pinfunction "P$29_P$29") (pintype "passive"))
      (node (ref "U$3") (pin "P$39") (pinfunction "P$39_P$39") (pintype "passive"))
    )
    (net (code "61") (name "Net-(U$3-PadP$20)") (class "Default")
      (node (ref "U$3") (pin "P$20") (pinfunction "P$20_P$20") (pintype "passive"))
      (node (ref "U$3") (pin "P$30") (pinfunction "P$30_P$30") (pintype "passive"))
      (node (ref "U$3") (pin "P$40") (pinfunction "P$40_P$40") (pintype "passive"))
    )
    (net (code "62") (name "Net-(U$3-PadP$41)") (class "Default")
      (node (ref "U$3") (pin "P$41") (pinfunction "P$41_P$41") (pintype "passive"))
      (node (ref "U$3") (pin "P$42") (pinfunction "P$42_P$42") (pintype "passive"))
      (node (ref "U$3") (pin "P$43") (pinfunction "P$43_P$43") (pintype "passive"))
      (node (ref "U$3") (pin "P$44") (pinfunction "P$44_P$44") (pintype "passive"))
      (node (ref "U$3") (pin "P$45") (pinfunction "P$45_P$45") (pintype "passive"))
      (node (ref "U$3") (pin "P$46") (pinfunction "P$46_P$46") (pintype "passive"))
      (node (ref "U$3") (pin "P$47") (pinfunction "P$47_P$47") (pintype "passive"))
      (node (ref "U$3") (pin "P$48") (pinfunction "P$48_P$48") (pintype "passive"))
      (node (ref "U$3") (pin "P$49") (pinfunction "P$49_P$49") (pintype "passive"))
      (node (ref "U$3") (pin "P$50") (pinfunction "P$50_P$50") (pintype "passive"))
    )
    (net (code "63") (name "Net-(U$3-PadP$51)") (class "Default")
      (node (ref "U$3") (pin "P$51") (pinfunction "P$51_P$51") (pintype "passive"))
      (node (ref "U$3") (pin "P$52") (pinfunction "P$52_P$52") (pintype "passive"))
      (node (ref "U$3") (pin "P$53") (pinfunction "P$53_P$53") (pintype "passive"))
      (node (ref "U$3") (pin "P$54") (pinfunction "P$54_P$54") (pintype "passive"))
      (node (ref "U$3") (pin "P$55") (pinfunction "P$55_P$55") (pintype "passive"))
      (node (ref "U$3") (pin "P$56") (pinfunction "P$56_P$56") (pintype "passive"))
      (node (ref "U$3") (pin "P$57") (pinfunction "P$57_P$57") (pintype "passive"))
      (node (ref "U$3") (pin "P$58") (pinfunction "P$58_P$58") (pintype "passive"))
      (node (ref "U$3") (pin "P$59") (pinfunction "P$59_P$59") (pintype "passive"))
      (node (ref "U$3") (pin "P$60") (pinfunction "P$60_P$60") (pintype "passive"))
    )
    (net (code "64") (name "Net-(U$3-PadP$61)") (class "Default")
      (node (ref "U$3") (pin "P$61") (pinfunction "P$61_P$61") (pintype "passive"))
      (node (ref "U$3") (pin "P$71") (pinfunction "P$71_P$71") (pintype "passive"))
      (node (ref "U$3") (pin "P$81") (pinfunction "P$81_P$81") (pintype "passive"))
      (node (ref "U$3") (pin "P$91") (pinfunction "P$91_P$91") (pintype "passive"))
    )
    (net (code "65") (name "Net-(U$3-PadP$62)") (class "Default")
      (node (ref "U$3") (pin "P$62") (pinfunction "P$62_P$62") (pintype "passive"))
      (node (ref "U$3") (pin "P$72") (pinfunction "P$72_P$72") (pintype "passive"))
      (node (ref "U$3") (pin "P$82") (pinfunction "P$82_P$82") (pintype "passive"))
      (node (ref "U$3") (pin "P$92") (pinfunction "P$92_P$92") (pintype "passive"))
    )
    (net (code "66") (name "Net-(U$3-PadP$63)") (class "Default")
      (node (ref "U$3") (pin "P$63") (pinfunction "P$63_P$63") (pintype "passive"))
      (node (ref "U$3") (pin "P$73") (pinfunction "P$73_P$73") (pintype "passive"))
      (node (ref "U$3") (pin "P$83") (pinfunction "P$83_P$83") (pintype "passive"))
      (node (ref "U$3") (pin "P$93") (pinfunction "P$93_P$93") (pintype "passive"))
    )
    (net (code "67") (name "Net-(U$3-PadP$64)") (class "Default")
      (node (ref "U$3") (pin "P$64") (pinfunction "P$64_P$64") (pintype "passive"))
      (node (ref "U$3") (pin "P$74") (pinfunction "P$74_P$74") (pintype "passive"))
      (node (ref "U$3") (pin "P$84") (pinfunction "P$84_P$84") (pintype "passive"))
      (node (ref "U$3") (pin "P$94") (pinfunction "P$94_P$94") (pintype "passive"))
    )
    (net (code "68") (name "Net-(U$3-PadP$65)") (class "Default")
      (node (ref "U$3") (pin "P$65") (pinfunction "P$65_P$65") (pintype "passive"))
      (node (ref "U$3") (pin "P$75") (pinfunction "P$75_P$75") (pintype "passive"))
      (node (ref "U$3") (pin "P$85") (pinfunction "P$85_P$85") (pintype "passive"))
      (node (ref "U$3") (pin "P$95") (pinfunction "P$95_P$95") (pintype "passive"))
    )
    (net (code "69") (name "Net-(U$3-PadP$66)") (class "Default")
      (node (ref "U$3") (pin "P$66") (pinfunction "P$66_P$66") (pintype "passive"))
      (node (ref "U$3") (pin "P$76") (pinfunction "P$76_P$76") (pintype "passive"))
      (node (ref "U$3") (pin "P$86") (pinfunction "P$86_P$86") (pintype "passive"))
      (node (ref "U$3") (pin "P$96") (pinfunction "P$96_P$96") (pintype "passive"))
    )
    (net (code "70") (name "Net-(U$3-PadP$67)") (class "Default")
      (node (ref "U$3") (pin "P$67") (pinfunction "P$67_P$67") (pintype "passive"))
      (node (ref "U$3") (pin "P$77") (pinfunction "P$77_P$77") (pintype "passive"))
      (node (ref "U$3") (pin "P$87") (pinfunction "P$87_P$87") (pintype "passive"))
      (node (ref "U$3") (pin "P$97") (pinfunction "P$97_P$97") (pintype "passive"))
    )
    (net (code "71") (name "Net-(U$3-PadP$68)") (class "Default")
      (node (ref "U$3") (pin "P$68") (pinfunction "P$68_P$68") (pintype "passive"))
      (node (ref "U$3") (pin "P$78") (pinfunction "P$78_P$78") (pintype "passive"))
      (node (ref "U$3") (pin "P$88") (pinfunction "P$88_P$88") (pintype "passive"))
      (node (ref "U$3") (pin "P$98") (pinfunction "P$98_P$98") (pintype "passive"))
    )
    (net (code "72") (name "Net-(U$3-PadP$69)") (class "Default")
      (node (ref "U$3") (pin "P$69") (pinfunction "P$69_P$69") (pintype "passive"))
      (node (ref "U$3") (pin "P$79") (pinfunction "P$79_P$79") (pintype "passive"))
      (node (ref "U$3") (pin "P$89") (pinfunction "P$89_P$89") (pintype "passive"))
      (node (ref "U$3") (pin "P$99") (pinfunction "P$99_P$99") (pintype "passive"))
    )
    (net (code "73") (name "Net-(U$3-PadP$100)") (class "Default")
      (node (ref "U$3") (pin "P$100") (pinfunction "P$100_P$100") (pintype "passive"))
      (node (ref "U$3") (pin "P$70") (pinfunction "P$70_P$70") (pintype "passive"))
      (node (ref "U$3") (pin "P$80") (pinfunction "P$80_P$80") (pintype "passive"))
      (node (ref "U$3") (pin "P$90") (pinfunction "P$90_P$90") (pintype "passive"))
    )
    (net (code "74") (name "Net-(U$4-Pad1)") (class "Default")
      (node (ref "U$4") (pin "1") (pinfunction "1_1") (pintype "bidirectional"))
      (node (ref "U$4") (pin "2") (pinfunction "2_2") (pintype "bidirectional"))
      (node (ref "U$4") (pin "3") (pinfunction "3_3") (pintype "bidirectional"))
    )
    (net (code "75") (name "Net-(U$5-Pad1)") (class "Default")
      (node (ref "U$5") (pin "1") (pinfunction "1_1") (pintype "bidirectional"))
      (node (ref "U$5") (pin "2") (pinfunction "2_2") (pintype "bidirectional"))
      (node (ref "U$5") (pin "3") (pinfunction "3_3") (pintype "bidirectional"))
    )
    (net (code "76") (name "Net-(U$6-Pad1)") (class "Default")
      (node (ref "U$6") (pin "1") (pinfunction "1_1") (pintype "bidirectional"))
      (node (ref "U$6") (pin "2") (pinfunction "2_2") (pintype "bidirectional"))
      (node (ref "U$6") (pin "3") (pinfunction "3_3") (pintype "bidirectional"))
    )
    (net (code "77") (name "Net-(U$7-Pad1)") (class "Default")
      (node (ref "U$7") (pin "1") (pinfunction "1_1") (pintype "bidirectional"))
      (node (ref "U$7") (pin "2") (pinfunction "2_2") (pintype "bidirectional"))
      (node (ref "U$7") (pin "3") (pinfunction "3_3") (pintype "bidirectional"))
    )
    (net (code "78") (name "Net-(U$8-Pad1)") (class "Default")
      (node (ref "U$8") (pin "1") (pinfunction "1_1") (pintype "bidirectional"))
      (node (ref "U$8") (pin "2") (pinfunction "2_2") (pintype "bidirectional"))
      (node (ref "U$8") (pin "3") (pinfunction "3_3") (pintype "bidirectional"))
    )
    (net (code "79") (name "Net-(U$9-Pad1)") (class "Default")
      (node (ref "U$9") (pin "1") (pinfunction "1_1") (pintype "bidirectional"))
      (node (ref "U$9") (pin "2") (pinfunction "2_2") (pintype "bidirectional"))
      (node (ref "U$9") (pin "3") (pinfunction "3_3") (pintype "bidirectional"))
    )
    (net (code "80") (name "Net-(U$10-Pad1)") (class "Default")
      (node (ref "U$10") (pin "1") (pinfunction "1_1") (pintype "bidirectional"))
      (node (ref "U$10") (pin "2") (pinfunction "2_2") (pintype "bidirectional"))
      (node (ref "U$10") (pin "3") (pinfunction "3_3") (pintype "bidirectional"))
    )
    (net (code "81") (name "Net-(U$11-Pad1)") (class "Default")
      (node (ref "U$11") (pin "1") (pinfunction "1_1") (pintype "bidirectional"))
      (node (ref "U$11") (pin "2") (pinfunction "2_2") (pintype "bidirectional"))
      (node (ref "U$11") (pin "3") (pinfunction "3_3") (pintype "bidirectional"))
    )
    (net (code "82") (name "Net-(U$12-Pad1)") (class "Default")
      (node (ref "U$12") (pin "1") (pinfunction "1_1") (pintype "bidirectional"))
      (node (ref "U$12") (pin "2") (pinfunction "2_2") (pintype "bidirectional"))
      (node (ref "U$12") (pin "3") (pinfunction "3_3") (pintype "bidirectional"))
    )
    (net (code "83") (name "Net-(U$13-Pad1)") (class "Default")
      (node (ref "U$13") (pin "1") (pinfunction "1_1") (pintype "bidirectional"))
      (node (ref "U$13") (pin "2") (pinfunction "2_2") (pintype "bidirectional"))
      (node (ref "U$13") (pin "3") (pinfunction "3_3") (pintype "bidirectional"))
    )
    (net (code "84") (name "Net-(U$14-Pad1)") (class "Default")
      (node (ref "U$14") (pin "1") (pinfunction "1_1") (pintype "bidirectional"))
      (node (ref "U$14") (pin "2") (pinfunction "2_2") (pintype "bidirectional"))
      (node (ref "U$14") (pin "3") (pinfunction "3_3") (pintype "bidirectional"))
    )
    (net (code "85") (name "Net-(U$15-Pad1)") (class "Default")
      (node (ref "U$15") (pin "1") (pinfunction "1_1") (pintype "bidirectional"))
      (node (ref "U$15") (pin "2") (pinfunction "2_2") (pintype "bidirectional"))
      (node (ref "U$15") (pin "3") (pinfunction "3_3") (pintype "bidirectional"))
    )
    (net (code "86") (name "Net-(U$16-Pad1)") (class "Default")
      (node (ref "U$16") (pin "1") (pinfunction "1_1") (pintype "bidirectional"))
      (node (ref "U$16") (pin "2") (pinfunction "2_2") (pintype "bidirectional"))
      (node (ref "U$16") (pin "3") (pinfunction "3_3") (pintype "bidirectional"))
    )
    (net (code "87") (name "Net-(U$17-Pad1)") (class "Default")
      (node (ref "U$17") (pin "1") (pinfunction "1_1") (pintype "bidirectional"))
      (node (ref "U$17") (pin "2") (pinfunction "2_2") (pintype "bidirectional"))
      (node (ref "U$17") (pin "3") (pinfunction "3_3") (pintype "bidirectional"))
    )
    (net (code "88") (name "Net-(U$18-Pad1)") (class "Default")
      (node (ref "U$18") (pin "1") (pinfunction "1_1") (pintype "bidirectional"))
      (node (ref "U$18") (pin "2") (pinfunction "2_2") (pintype "bidirectional"))
      (node (ref "U$18") (pin "3") (pinfunction "3_3") (pintype "bidirectional"))
    )
    (net (code "89") (name "Net-(U$19-Pad1)") (class "Default")
      (node (ref "U$19") (pin "1") (pinfunction "1_1") (pintype "bidirectional"))
      (node (ref "U$19") (pin "2") (pinfunction "2_2") (pintype "bidirectional"))
      (node (ref "U$19") (pin "3") (pinfunction "3_3") (pintype "bidirectional"))
    )
    (net (code "90") (name "RTS#") (class "Default")
      (node (ref "C3") (pin "1") (pinfunction "1_1") (pintype "passive"))
      (node (ref "JP3") (pin "6") (pinfunction "6_6") (pintype "passive"))
    )
    (net (code "91") (name "VCC") (class "Default")
      (node (ref "AVCC") (pin "1") (pinfunction "1_1") (pintype "passive"))
      (node (ref "AVCC") (pin "2") (pinfunction "2_2") (pintype "passive"))
      (node (ref "AVCC") (pin "3") (pinfunction "3_3") (pintype "passive"))
      (node (ref "IC1") (pin "20") (pinfunction "AVCC_20") (pintype "bidirectional"))
      (node (ref "IC1") (pin "7") (pinfunction "VCC_7") (pintype "bidirectional"))
      (node (ref "J3") (pin "2") (pinfunction "2_2") (pintype "passive"))
      (node (ref "JP4") (pin "2") (pinfunction "2_2") (pintype "passive"))
      (node (ref "R1") (pin "1") (pinfunction "1_1") (pintype "passive"))
      (node (ref "R2") (pin "2") (pinfunction "2_2") (pintype "passive"))
      (node (ref "U$1") (pin "P$1") (pinfunction "1_P$1") (pintype "passive"))
      (node (ref "U$1") (pin "P$10") (pinfunction "P$10_P$10") (pintype "passive"))
      (node (ref "U$1") (pin "P$2") (pinfunction "5_P$2") (pintype "passive"))
      (node (ref "U$1") (pin "P$3") (pinfunction "P$3_P$3") (pintype "passive"))
      (node (ref "U$1") (pin "P$4") (pinfunction "P$4_P$4") (pintype "passive"))
      (node (ref "U$1") (pin "P$5") (pinfunction "P$5_P$5") (pintype "passive"))
      (node (ref "U$1") (pin "P$6") (pinfunction "P$6_P$6") (pintype "passive"))
      (node (ref "U$1") (pin "P$7") (pinfunction "P$7_P$7") (pintype "passive"))
      (node (ref "U$1") (pin "P$8") (pinfunction "P$8_P$8") (pintype "passive"))
      (node (ref "U$1") (pin "P$9") (pinfunction "P$9_P$9") (pintype "passive"))
      (node (ref "VCC") (pin "1") (pinfunction "1_1") (pintype "passive"))
      (node (ref "VCC") (pin "2") (pinfunction "2_2") (pintype "passive"))
      (node (ref "VCC") (pin "3") (pinfunction "3_3") (pintype "passive"))
    )
    (net (code "92") (name "VIN") (class "Default")
      (node (ref "C1") (pin "1") (pinfunction "+_1") (pintype "passive"))
      (node (ref "IC2") (pin "1") (pinfunction "VI_1") (pintype "input"))
      (node (ref "S1") (pin "3") (pinfunction "S_3") (pintype "passive"))
      (node (ref "VIN") (pin "1") (pinfunction "1_1") (pintype "passive"))
      (node (ref "VIN") (pin "2") (pinfunction "2_2") (pintype "passive"))
      (node (ref "VIN") (pin "3") (pinfunction "3_3") (pintype "passive"))
    )
    (net (code "93") (name "unconnected-(J1-CDN-Pad-2)") (class "Default")
      (node (ref "J1") (pin "-2") (pinfunction "CDN_-2") (pintype "bidirectional"))
    )
    (net (code "94") (name "unconnected-(S1-O-Pad1)") (class "Default")
      (node (ref "S1") (pin "1") (pinfunction "O_1") (pintype "passive"))
    )
  )
)
